# attiny4.net
KiCad netlist of a schematic drawn in EAGLE
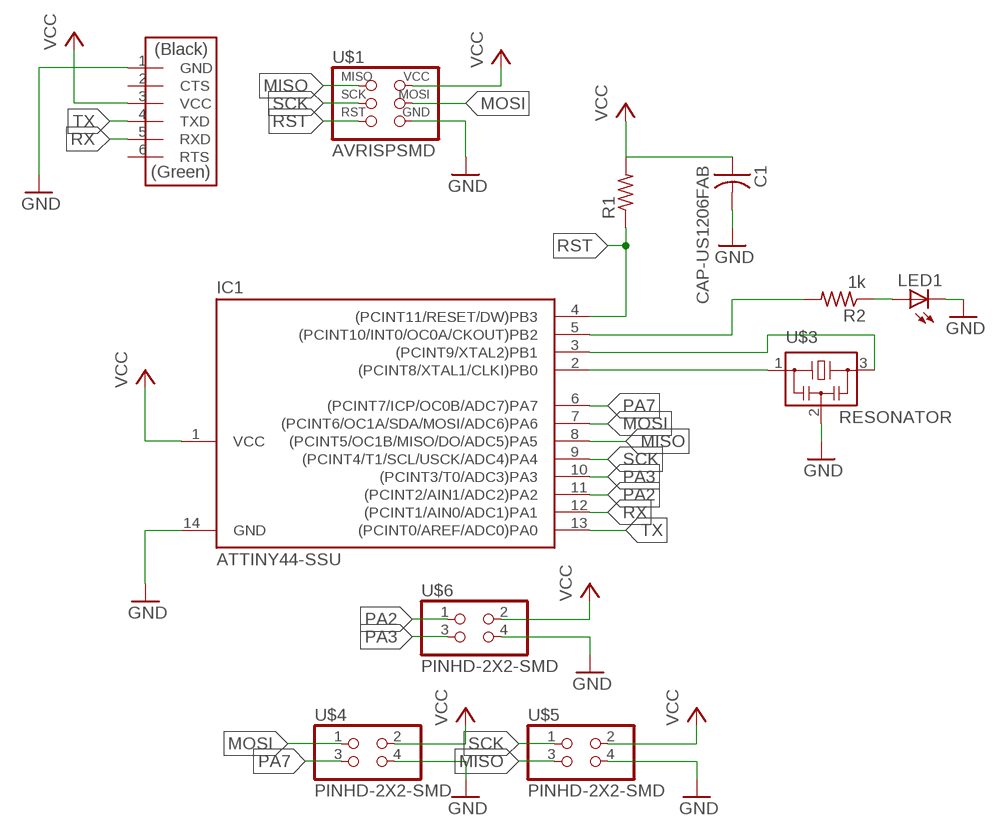
[diagram p0: schematic, sheet 1]

(export (version "E")
  (design (tool "Eeschema 10.0.6"))
  (components
    (comp (ref "C1")
      (value "CAP-US1206FAB")
      (footprint "eagle-import:C1206FAB")
      (libsource (lib "eagle-import") (part "CAP-US1206FAB"))
    )
    (comp (ref "IC1")
      (value "ATTINY44-SSU")
      (footprint "eagle-import:SOIC14")
      (libsource (lib "eagle-import") (part "ATTINY44-SSU"))
    )
    (comp (ref "LED1")
      (value "LEDSML1206")
      (footprint "eagle-import:SML1206")
      (libsource (lib "eagle-import") (part "LEDSML1206"))
    )
    (comp (ref "R1")
      (value "RES-US1206FAB")
      (footprint "eagle-import:R1206FAB")
      (libsource (lib "eagle-import") (part "RES-US1206FAB"))
    )
    (comp (ref "R2")
      (value "1k")
      (footprint "eagle-import:R1206FAB")
      (libsource (lib "eagle-import") (part "RES-US1206FAB"))
    )
    (comp (ref "U$1")
      (value "AVRISPSMD")
      (footprint "eagle-import:2X03SMD")
      (libsource (lib "eagle-import") (part "AVRISPSMD"))
    )
    (comp (ref "U$2")
      (value "FTDI-SMD-HEADER")
      (footprint "eagle-import:1X06SMD")
      (libsource (lib "eagle-import") (part "FTDI-SMD-HEADER"))
    )
    (comp (ref "U$3")
      (value "RESONATOR")
      (footprint "eagle-import:EFOBM")
      (libsource (lib "eagle-import") (part "RESONATOR"))
    )
    (comp (ref "U$4")
      (value "PINHD-2X2-SMD")
      (footprint "eagle-import:2X02SMD")
      (libsource (lib "eagle-import") (part "PINHD-2X2-SMD"))
    )
    (comp (ref "U$5")
      (value "PINHD-2X2-SMD")
      (footprint "eagle-import:2X02SMD")
      (libsource (lib "eagle-import") (part "PINHD-2X2-SMD"))
    )
    (comp (ref "U$6")
      (value "PINHD-2X2-SMD")
      (footprint "eagle-import:2X02SMD")
      (libsource (lib "eagle-import") (part "PINHD-2X2-SMD"))
    )
  )
  (nets
    (net (code "1") (name "GND") (class "Default")
      (node (ref "C1") (pin "2") (pinfunction "2_2") (pintype "passive"))
      (node (ref "IC1") (pin "14") (pinfunction "GND_14") (pintype "power_in"))
      (node (ref "LED1") (pin "C") (pinfunction "C_C") (pintype "passive"))
      (node (ref "U$1") (pin "6") (pinfunction "GND_6") (pintype "passive"))
      (node (ref "U$2") (pin "1") (pinfunction "GND_1") (pintype "bidirectional"))
      (node (ref "U$3") (pin "2") (pinfunction "2_2") (pintype "passive"))
      (node (ref "U$4") (pin "4") (pinfunction "4_4") (pintype "passive"))
      (node (ref "U$5") (pin "4") (pinfunction "4_4") (pintype "passive"))
      (node (ref "U$6") (pin "4") (pinfunction "4_4") (pintype "passive"))
    )
    (net (code "2") (name "MISO") (class "Default")
      (node (ref "IC1") (pin "8") (pinfunction "(PCINT5/OC1B/MISO/DO/ADC5)PA5_8") (pintype "bidirectional"))
      (node (ref "U$1") (pin "1") (pinfunction "MISO_1") (pintype "passive"))
      (node (ref "U$5") (pin "3") (pinfunction "3_3") (pintype "passive"))
    )
    (net (code "3") (name "MOSI") (class "Default")
      (node (ref "IC1") (pin "7") (pinfunction "(PCINT6/OC1A/SDA/MOSI/ADC6)PA6_7") (pintype "bidirectional"))
      (node (ref "U$1") (pin "4") (pinfunction "MOSI_4") (pintype "passive"))
      (node (ref "U$4") (pin "1") (pinfunction "1_1") (pintype "passive"))
    )
    (net (code "4") (name "Net-(IC1-(PCINT8{slash}XTAL1{slash}CLKI)PB0)") (class "Default")
      (node (ref "IC1") (pin "2") (pinfunction "(PCINT8/XTAL1/CLKI)PB0_2") (pintype "bidirectional"))
      (node (ref "U$3") (pin "1") (pinfunction "1_1") (pintype "passive"))
    )
    (net (code "5") (name "Net-(IC1-(PCINT9{slash}XTAL2)PB1)") (class "Default")
      (node (ref "IC1") (pin "3") (pinfunction "(PCINT9/XTAL2)PB1_3") (pintype "bidirectional"))
      (node (ref "U$3") (pin "3") (pinfunction "3_3") (pintype "passive"))
    )
    (net (code "6") (name "Net-(IC1-(PCINT10{slash}INT0{slash}OC0A{slash}CKOUT)PB2)") (class "Default")
      (node (ref "IC1") (pin "5") (pinfunction "(PCINT10/INT0/OC0A/CKOUT)PB2_5") (pintype "bidirectional"))
      (node (ref "R2") (pin "2") (pinfunction "2_2") (pintype "passive"))
    )
    (net (code "7") (name "Net-(LED1-PadA)") (class "Default")
      (node (ref "LED1") (pin "A") (pinfunction "A_A") (pintype "passive"))
      (node (ref "R2") (pin "1") (pinfunction "1_1") (pintype "passive"))
    )
    (net (code "8") (name "PA2") (class "Default")
      (node (ref "IC1") (pin "11") (pinfunction "(PCINT2/AIN1/ADC2)PA2_11") (pintype "bidirectional"))
      (node (ref "U$6") (pin "1") (pinfunction "1_1") (pintype "passive"))
    )
    (net (code "9") (name "PA3") (class "Default")
      (node (ref "IC1") (pin "10") (pinfunction "(PCINT3/T0/ADC3)PA3_10") (pintype "bidirectional"))
      (node (ref "U$6") (pin "3") (pinfunction "3_3") (pintype "passive"))
    )
    (net (code "10") (name "PA7") (class "Default")
      (node (ref "IC1") (pin "6") (pinfunction "(PCINT7/ICP/OC0B/ADC7)PA7_6") (pintype "bidirectional"))
      (node (ref "U$4") (pin "3") (pinfunction "3_3") (pintype "passive"))
    )
    (net (code "11") (name "RST") (class "Default")
      (node (ref "IC1") (pin "4") (pinfunction "(PCINT11/RESET/DW)PB3_4") (pintype "bidirectional"))
      (node (ref "R1") (pin "1") (pinfunction "1_1") (pintype "passive"))
      (node (ref "U$1") (pin "5") (pinfunction "RST_5") (pintype "passive"))
    )
    (net (code "12") (name "RX") (class "Default")
      (node (ref "IC1") (pin "12") (pinfunction "(PCINT1/AIN0/ADC1)PA1_12") (pintype "bidirectional"))
      (node (ref "U$2") (pin "5") (pinfunction "RXD_5") (pintype "bidirectional"))
    )
    (net (code "13") (name "SCK") (class "Default")
      (node (ref "IC1") (pin "9") (pinfunction "(PCINT4/T1/SCL/USCK/ADC4)PA4_9") (pintype "bidirectional"))
      (node (ref "U$1") (pin "3") (pinfunction "SCK_3") (pintype "passive"))
      (node (ref "U$5") (pin "1") (pinfunction "1_1") (pintype "passive"))
    )
    (net (code "14") (name "TX") (class "Default")
      (node (ref "IC1") (pin "13") (pinfunction "(PCINT0/AREF/ADC0)PA0_13") (pintype "bidirectional"))
      (node (ref "U$2") (pin "4") (pinfunction "TXD_4") (pintype "bidirectional"))
    )
    (net (code "15") (name "VCC") (class "Default")
      (node (ref "C1") (pin "1") (pinfunction "1_1") (pintype "passive"))
      (node (ref "IC1") (pin "1") (pinfunction "VCC_1") (pintype "power_in"))
      (node (ref "R1") (pin "2") (pinfunction "2_2") (pintype "passive"))
      (node (ref "U$1") (pin "2") (pinfunction "VCC_2") (pintype "passive"))
      (node (ref "U$2") (pin "3") (pinfunction "VCC_3") (pintype "bidirectional"))
      (node (ref "U$4") (pin "2") (pinfunction "2_2") (pintype "passive"))
      (node (ref "U$5") (pin "2") (pinfunction "2_2") (pintype "passive"))
      (node (ref "U$6") (pin "2") (pinfunction "2_2") (pintype "passive"))
    )
    (net (code "16") (name "unconnected-(U$2-CTS-Pad2)") (class "Default")
      (node (ref "U$2") (pin "2") (pinfunction "CTS_2") (pintype "bidirectional"))
    )
    (net (code "17") (name "unconnected-(U$2-RTS-Pad6)") (class "Default")
      (node (ref "U$2") (pin "6") (pinfunction "RTS_6") (pintype "bidirectional"))
    )
  )
)
